# headset-btmodule.net
KiCad netlist of a schematic drawn in EAGLE
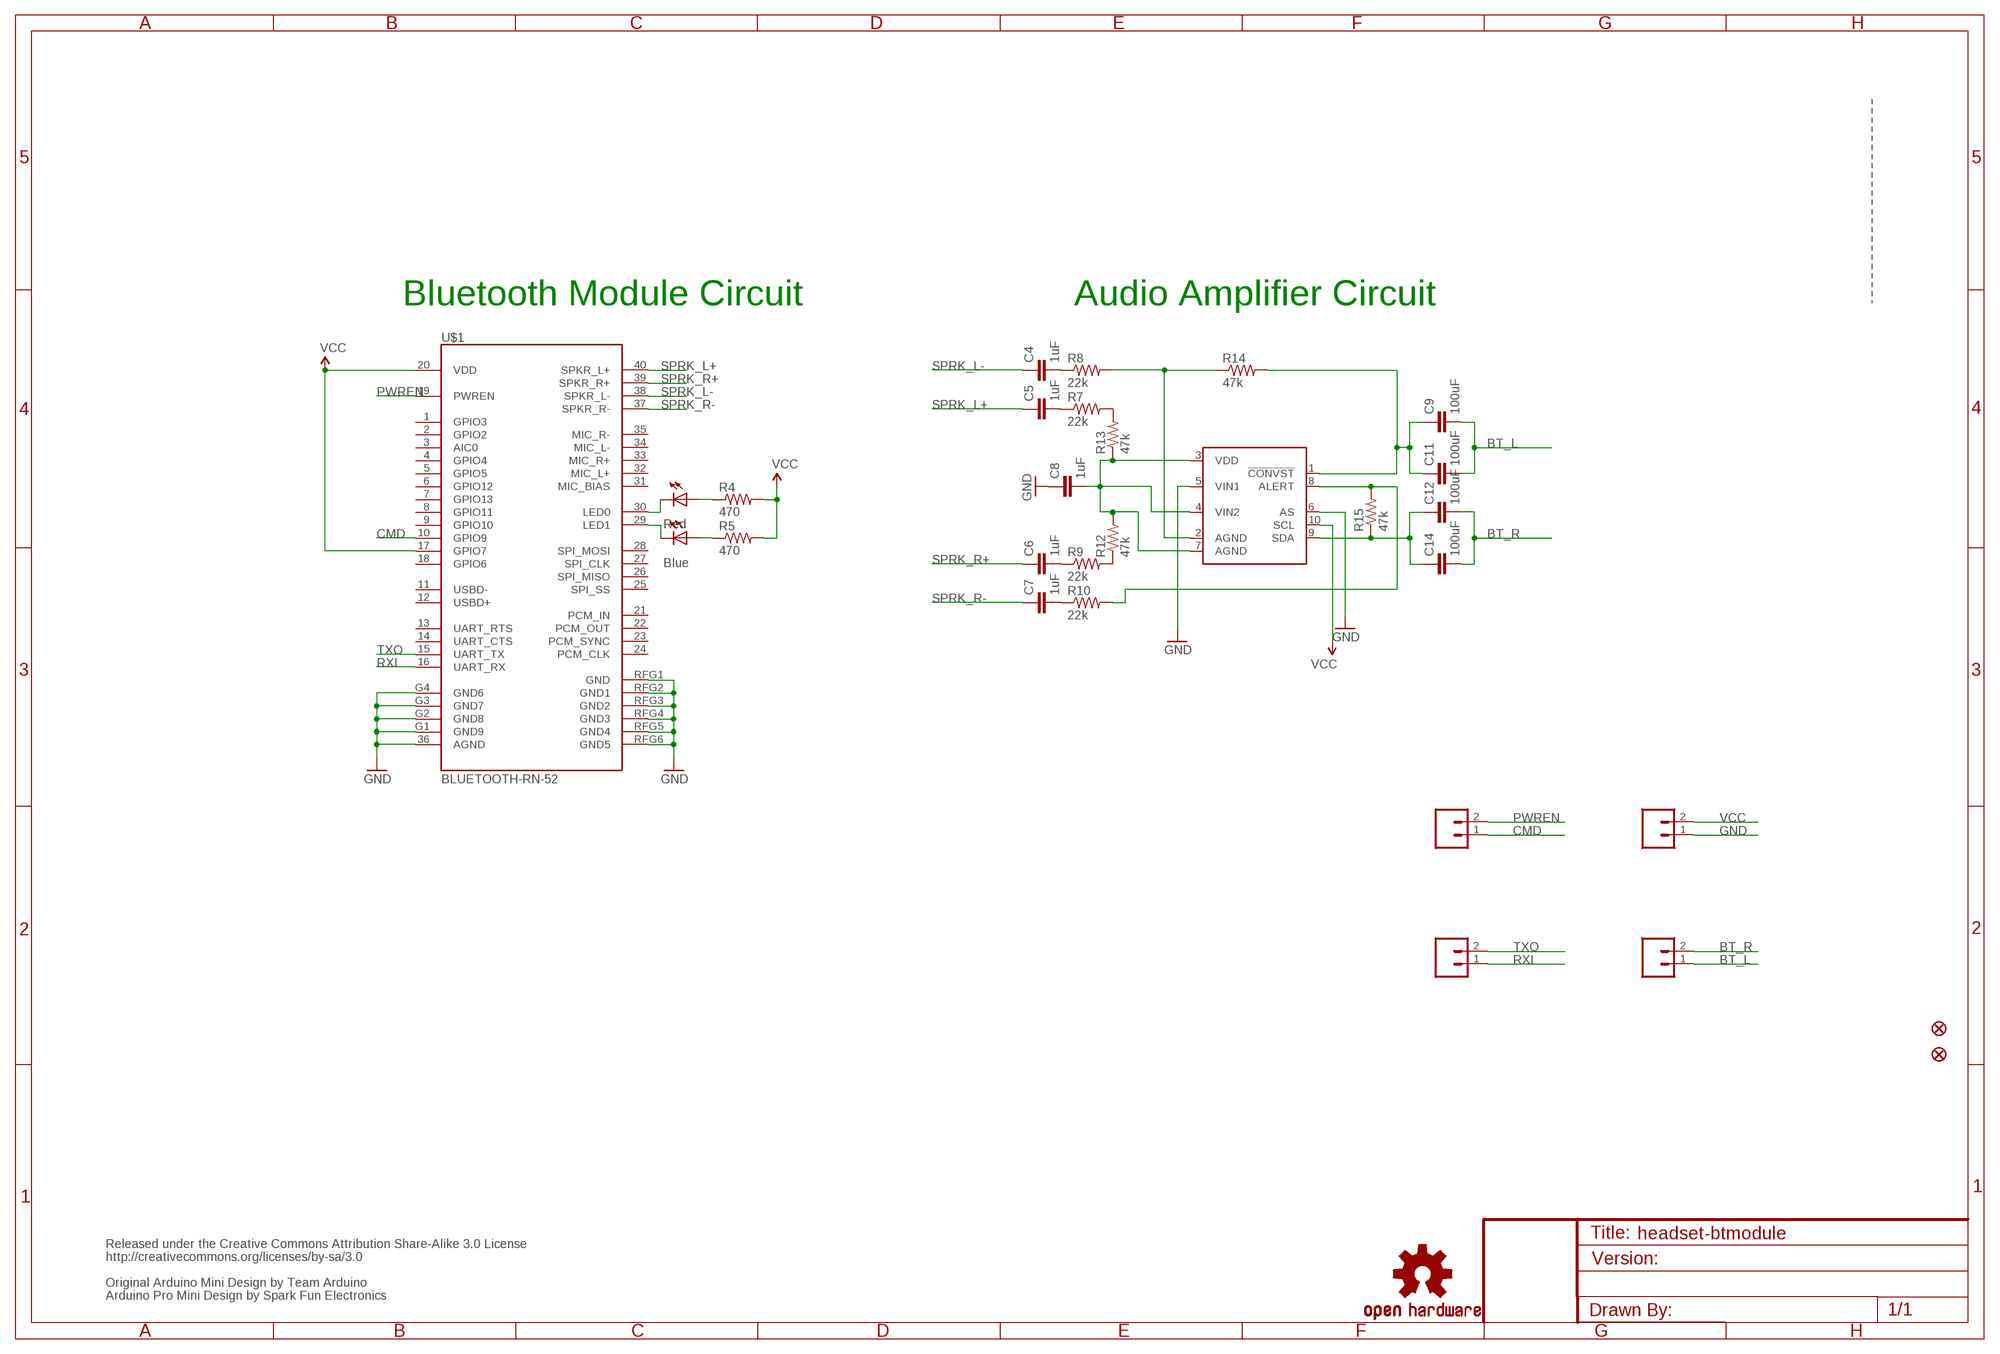
[diagram p0: schematic, sheet 1]

(export (version "E")
  (design (tool "Eeschema 10.0.6"))
  (components
    (comp (ref "AUDIO")
      (value "M02PTH")
      (footprint "eagle-import:1X02")
      (libsource (lib "eagle-import") (part "M02PTH"))
    )
    (comp (ref "C4")
      (value "1uF")
      (footprint "eagle-import:0402-CAP")
      (libsource (lib "eagle-import") (part "CAP0402-CAP"))
    )
    (comp (ref "C5")
      (value "1uF")
      (footprint "eagle-import:0402-CAP")
      (libsource (lib "eagle-import") (part "CAP0402-CAP"))
    )
    (comp (ref "C6")
      (value "1uF")
      (footprint "eagle-import:0402-CAP")
      (libsource (lib "eagle-import") (part "CAP0402-CAP"))
    )
    (comp (ref "C7")
      (value "1uF")
      (footprint "eagle-import:0402-CAP")
      (libsource (lib "eagle-import") (part "CAP0402-CAP"))
    )
    (comp (ref "C8")
      (value "1uF")
      (footprint "eagle-import:0402-CAP")
      (libsource (lib "eagle-import") (part "CAP0402-CAP"))
    )
    (comp (ref "C9")
      (value "100uF")
      (footprint "eagle-import:0805")
      (libsource (lib "eagle-import") (part "CAP0805"))
    )
    (comp (ref "C11")
      (value "100uF")
      (footprint "eagle-import:0805")
      (libsource (lib "eagle-import") (part "CAP0805"))
    )
    (comp (ref "C12")
      (value "100uF")
      (footprint "eagle-import:0805")
      (libsource (lib "eagle-import") (part "CAP0805"))
    )
    (comp (ref "C14")
      (value "100uF")
      (footprint "eagle-import:0805")
      (libsource (lib "eagle-import") (part "CAP0805"))
    )
    (comp (ref "CMD")
      (value "M02PTH")
      (footprint "eagle-import:1X02")
      (libsource (lib "eagle-import") (part "M02PTH"))
    )
    (comp (ref "JP5")
      (value "FIDUCIALUFIDUCIAL")
      (footprint "eagle-import:MICRO-FIDUCIAL")
      (libsource (lib "eagle-import") (part "FIDUCIALUFIDUCIAL"))
    )
    (comp (ref "JP8")
      (value "FIDUCIALUFIDUCIAL")
      (footprint "eagle-import:MICRO-FIDUCIAL")
      (libsource (lib "eagle-import") (part "FIDUCIALUFIDUCIAL"))
    )
    (comp (ref "LED3")
      (value "Red")
      (footprint "eagle-import:LED3MM-NS")
      (libsource (lib "eagle-import") (part "LED-3MM-NO_SILK"))
    )
    (comp (ref "LED4")
      (value "Blue")
      (footprint "eagle-import:LED3MM-NS")
      (libsource (lib "eagle-import") (part "LED-3MM-NO_SILK"))
    )
    (comp (ref "POWER")
      (value "M02PTH")
      (footprint "eagle-import:1X02")
      (libsource (lib "eagle-import") (part "M02PTH"))
    )
    (comp (ref "R4")
      (value "470")
      (footprint "eagle-import:0402-RES")
      (libsource (lib "eagle-import") (part "RESISTOR0402-RES"))
    )
    (comp (ref "R5")
      (value "470")
      (footprint "eagle-import:0402-RES")
      (libsource (lib "eagle-import") (part "RESISTOR0402-RES"))
    )
    (comp (ref "R7")
      (value "22k")
      (footprint "eagle-import:0402-RES")
      (libsource (lib "eagle-import") (part "RESISTOR0402-RES"))
    )
    (comp (ref "R8")
      (value "22k")
      (footprint "eagle-import:0402-RES")
      (libsource (lib "eagle-import") (part "RESISTOR0402-RES"))
    )
    (comp (ref "R9")
      (value "22k")
      (footprint "eagle-import:0402-RES")
      (libsource (lib "eagle-import") (part "RESISTOR0402-RES"))
    )
    (comp (ref "R10")
      (value "22k")
      (footprint "eagle-import:0402-RES")
      (libsource (lib "eagle-import") (part "RESISTOR0402-RES"))
    )
    (comp (ref "R12")
      (value "47k")
      (footprint "eagle-import:0402-RES")
      (libsource (lib "eagle-import") (part "RESISTOR0402-RES"))
    )
    (comp (ref "R13")
      (value "47k")
      (footprint "eagle-import:0402-RES")
      (libsource (lib "eagle-import") (part "RESISTOR0402-RES"))
    )
    (comp (ref "R14")
      (value "47k")
      (footprint "eagle-import:0402-RES")
      (libsource (lib "eagle-import") (part "RESISTOR0402-RES"))
    )
    (comp (ref "R15")
      (value "47k")
      (footprint "eagle-import:0402-RES")
      (libsource (lib "eagle-import") (part "RESISTOR0402-RES"))
    )
    (comp (ref "T")
      (value "AD7992")
      (footprint "eagle-import:MSOP10")
      (fields (field (name "MPN") "AD7992BRMZ-0"))
      (libsource (lib "eagle-import") (part "AD7992"))
    )
    (comp (ref "TX")
      (value "M02PTH")
      (footprint "eagle-import:1X02")
      (libsource (lib "eagle-import") (part "M02PTH"))
    )
    (comp (ref "U$1")
      (value "BLUETOOTH-RN-52")
      (footprint "eagle-import:RN-52")
      (libsource (lib "eagle-import") (part "BLUETOOTH-RN-52"))
    )
    (comp (ref "U$3")
      (value "OSHW-LOGOS")
      (footprint "eagle-import:OSHW-LOGO-S")
      (libsource (lib "eagle-import") (part "OSHW-LOGOS"))
    )
  )
  (nets
    (net (code "1") (name "/BT_L") (class "Default")
      (node (ref "AUDIO") (pin "1") (pinfunction "1_1") (pintype "passive"))
      (node (ref "C11") (pin "2") (pinfunction "2_2") (pintype "passive"))
      (node (ref "C9") (pin "2") (pinfunction "2_2") (pintype "passive"))
    )
    (net (code "2") (name "/BT_R") (class "Default")
      (node (ref "AUDIO") (pin "2") (pinfunction "2_2") (pintype "passive"))
      (node (ref "C12") (pin "2") (pinfunction "2_2") (pintype "passive"))
      (node (ref "C14") (pin "2") (pinfunction "2_2") (pintype "passive"))
    )
    (net (code "3") (name "/CMD") (class "Default")
      (node (ref "CMD") (pin "1") (pinfunction "1_1") (pintype "passive"))
      (node (ref "U$1") (pin "10") (pinfunction "GPIO9_10") (pintype "bidirectional"))
    )
    (net (code "4") (name "/PWREN") (class "Default")
      (node (ref "CMD") (pin "2") (pinfunction "2_2") (pintype "passive"))
      (node (ref "U$1") (pin "19") (pinfunction "PWREN_19") (pintype "bidirectional"))
    )
    (net (code "5") (name "/RXI") (class "Default")
      (node (ref "TX") (pin "1") (pinfunction "1_1") (pintype "passive"))
      (node (ref "U$1") (pin "16") (pinfunction "UART_RX_16") (pintype "bidirectional"))
    )
    (net (code "6") (name "/SPRK_L+") (class "Default")
      (node (ref "C5") (pin "1") (pinfunction "1_1") (pintype "passive"))
      (node (ref "U$1") (pin "40") (pinfunction "SPKR_L+_40") (pintype "bidirectional"))
    )
    (net (code "7") (name "/SPRK_L-") (class "Default")
      (node (ref "C4") (pin "1") (pinfunction "1_1") (pintype "passive"))
      (node (ref "U$1") (pin "38") (pinfunction "SPKR_L-_38") (pintype "bidirectional"))
    )
    (net (code "8") (name "/SPRK_R+") (class "Default")
      (node (ref "C6") (pin "1") (pinfunction "1_1") (pintype "passive"))
      (node (ref "U$1") (pin "39") (pinfunction "SPKR_R+_39") (pintype "bidirectional"))
    )
    (net (code "9") (name "/SPRK_R-") (class "Default")
      (node (ref "C7") (pin "1") (pinfunction "1_1") (pintype "passive"))
      (node (ref "U$1") (pin "37") (pinfunction "SPKR_R-_37") (pintype "bidirectional"))
    )
    (net (code "10") (name "/TXO") (class "Default")
      (node (ref "TX") (pin "2") (pinfunction "2_2") (pintype "passive"))
      (node (ref "U$1") (pin "15") (pinfunction "UART_TX_15") (pintype "bidirectional"))
    )
    (net (code "11") (name "GND") (class "Default")
      (node (ref "C8") (pin "1") (pinfunction "1_1") (pintype "passive"))
      (node (ref "POWER") (pin "1") (pinfunction "1_1") (pintype "passive"))
      (node (ref "T") (pin "5") (pinfunction "VIN1_5") (pintype "input"))
      (node (ref "T") (pin "6") (pinfunction "AS_6") (pintype "input"))
      (node (ref "U$1") (pin "36") (pinfunction "AGND_36") (pintype "bidirectional"))
      (node (ref "U$1") (pin "G1") (pinfunction "GND9_G1") (pintype "bidirectional"))
      (node (ref "U$1") (pin "G2") (pinfunction "GND8_G2") (pintype "bidirectional"))
      (node (ref "U$1") (pin "G3") (pinfunction "GND7_G3") (pintype "bidirectional"))
      (node (ref "U$1") (pin "G4") (pinfunction "GND6_G4") (pintype "bidirectional"))
      (node (ref "U$1") (pin "RFG1") (pinfunction "GND_RFG1") (pintype "bidirectional"))
      (node (ref "U$1") (pin "RFG2") (pinfunction "GND1_RFG2") (pintype "bidirectional"))
      (node (ref "U$1") (pin "RFG3") (pinfunction "GND2_RFG3") (pintype "bidirectional"))
      (node (ref "U$1") (pin "RFG4") (pinfunction "GND3_RFG4") (pintype "bidirectional"))
      (node (ref "U$1") (pin "RFG5") (pinfunction "GND4_RFG5") (pintype "bidirectional"))
      (node (ref "U$1") (pin "RFG6") (pinfunction "GND5_RFG6") (pintype "bidirectional"))
    )
    (net (code "12") (name "Net-(C4-Pad2)") (class "Default")
      (node (ref "C4") (pin "2") (pinfunction "2_2") (pintype "passive"))
      (node (ref "R8") (pin "1") (pinfunction "1_1") (pintype "passive"))
    )
    (net (code "13") (name "Net-(C5-Pad2)") (class "Default")
      (node (ref "C5") (pin "2") (pinfunction "2_2") (pintype "passive"))
      (node (ref "R7") (pin "1") (pinfunction "1_1") (pintype "passive"))
    )
    (net (code "14") (name "Net-(C6-Pad2)") (class "Default")
      (node (ref "C6") (pin "2") (pinfunction "2_2") (pintype "passive"))
      (node (ref "R9") (pin "1") (pinfunction "1_1") (pintype "passive"))
    )
    (net (code "15") (name "Net-(C7-Pad2)") (class "Default")
      (node (ref "C7") (pin "2") (pinfunction "2_2") (pintype "passive"))
      (node (ref "R10") (pin "1") (pinfunction "1_1") (pintype "passive"))
    )
    (net (code "16") (name "Net-(LED3-C)") (class "Default")
      (node (ref "LED3") (pin "K") (pinfunction "C_K") (pintype "passive"))
      (node (ref "U$1") (pin "30") (pinfunction "LED0_30") (pintype "bidirectional"))
    )
    (net (code "17") (name "Net-(LED3-PadA)") (class "Default")
      (node (ref "LED3") (pin "A") (pinfunction "A_A") (pintype "passive"))
      (node (ref "R4") (pin "1") (pinfunction "1_1") (pintype "passive"))
    )
    (net (code "18") (name "Net-(LED4-C)") (class "Default")
      (node (ref "LED4") (pin "K") (pinfunction "C_K") (pintype "passive"))
      (node (ref "U$1") (pin "29") (pinfunction "LED1_29") (pintype "bidirectional"))
    )
    (net (code "19") (name "Net-(LED4-PadA)") (class "Default")
      (node (ref "LED4") (pin "A") (pinfunction "A_A") (pintype "passive"))
      (node (ref "R5") (pin "1") (pinfunction "1_1") (pintype "passive"))
    )
    (net (code "20") (name "Net-(R12-Pad1)") (class "Default")
      (node (ref "R12") (pin "1") (pinfunction "1_1") (pintype "passive"))
      (node (ref "R9") (pin "2") (pinfunction "2_2") (pintype "passive"))
    )
    (net (code "21") (name "Net-(R13-Pad2)") (class "Default")
      (node (ref "R13") (pin "2") (pinfunction "2_2") (pintype "passive"))
      (node (ref "R7") (pin "2") (pinfunction "2_2") (pintype "passive"))
    )
    (net (code "22") (name "Net-(R14-Pad1)") (class "Default")
      (node (ref "R14") (pin "1") (pinfunction "1_1") (pintype "passive"))
      (node (ref "R8") (pin "2") (pinfunction "2_2") (pintype "passive"))
      (node (ref "T") (pin "2") (pinfunction "AGND_2") (pintype "power_in"))
    )
    (net (code "23") (name "Net-(T-ALERT)") (class "Default")
      (node (ref "R10") (pin "2") (pinfunction "2_2") (pintype "passive"))
      (node (ref "R15") (pin "2") (pinfunction "2_2") (pintype "passive"))
      (node (ref "T") (pin "8") (pinfunction "ALERT_8") (pintype "output"))
    )
    (net (code "24") (name "Net-(T-SDA)") (class "Default")
      (node (ref "C12") (pin "1") (pinfunction "1_1") (pintype "passive"))
      (node (ref "C14") (pin "1") (pinfunction "1_1") (pintype "passive"))
      (node (ref "R15") (pin "1") (pinfunction "1_1") (pintype "passive"))
      (node (ref "T") (pin "9") (pinfunction "SDA_9") (pintype "bidirectional"))
    )
    (net (code "25") (name "Net-(T-VDD)") (class "Default")
      (node (ref "C8") (pin "2") (pinfunction "2_2") (pintype "passive"))
      (node (ref "R12") (pin "2") (pinfunction "2_2") (pintype "passive"))
      (node (ref "R13") (pin "1") (pinfunction "1_1") (pintype "passive"))
      (node (ref "T") (pin "3") (pinfunction "VDD_3") (pintype "power_in"))
      (node (ref "T") (pin "4") (pinfunction "VIN2_4") (pintype "input"))
      (node (ref "T") (pin "7") (pinfunction "AGND_7") (pintype "power_in"))
    )
    (net (code "26") (name "Net-(T-~{CONVST})") (class "Default")
      (node (ref "C11") (pin "1") (pinfunction "1_1") (pintype "passive"))
      (node (ref "C9") (pin "1") (pinfunction "1_1") (pintype "passive"))
      (node (ref "R14") (pin "2") (pinfunction "2_2") (pintype "passive"))
      (node (ref "T") (pin "1") (pinfunction "~{CONVST}_1") (pintype "input"))
    )
    (net (code "27") (name "VCC") (class "Default")
      (node (ref "POWER") (pin "2") (pinfunction "2_2") (pintype "passive"))
      (node (ref "R4") (pin "2") (pinfunction "2_2") (pintype "passive"))
      (node (ref "R5") (pin "2") (pinfunction "2_2") (pintype "passive"))
      (node (ref "T") (pin "10") (pinfunction "SCL_10") (pintype "input"))
      (node (ref "U$1") (pin "17") (pinfunction "GPIO7_17") (pintype "bidirectional"))
      (node (ref "U$1") (pin "20") (pinfunction "VDD_20") (pintype "bidirectional"))
    )
    (net (code "28") (name "unconnected-(U$1-AIC0-Pad3)") (class "Default")
      (node (ref "U$1") (pin "3") (pinfunction "AIC0_3") (pintype "bidirectional"))
    )
    (net (code "29") (name "unconnected-(U$1-GPIO2-Pad2)") (class "Default")
      (node (ref "U$1") (pin "2") (pinfunction "GPIO2_2") (pintype "bidirectional"))
    )
    (net (code "30") (name "unconnected-(U$1-GPIO3-Pad1)") (class "Default")
      (node (ref "U$1") (pin "1") (pinfunction "GPIO3_1") (pintype "bidirectional"))
    )
    (net (code "31") (name "unconnected-(U$1-GPIO4-Pad4)") (class "Default")
      (node (ref "U$1") (pin "4") (pinfunction "GPIO4_4") (pintype "bidirectional"))
    )
    (net (code "32") (name "unconnected-(U$1-GPIO5-Pad5)") (class "Default")
      (node (ref "U$1") (pin "5") (pinfunction "GPIO5_5") (pintype "bidirectional"))
    )
    (net (code "33") (name "unconnected-(U$1-GPIO6-Pad18)") (class "Default")
      (node (ref "U$1") (pin "18") (pinfunction "GPIO6_18") (pintype "bidirectional"))
    )
    (net (code "34") (name "unconnected-(U$1-GPIO10-Pad9)") (class "Default")
      (node (ref "U$1") (pin "9") (pinfunction "GPIO10_9") (pintype "bidirectional"))
    )
    (net (code "35") (name "unconnected-(U$1-GPIO11-Pad8)") (class "Default")
      (node (ref "U$1") (pin "8") (pinfunction "GPIO11_8") (pintype "bidirectional"))
    )
    (net (code "36") (name "unconnected-(U$1-GPIO12-Pad6)") (class "Default")
      (node (ref "U$1") (pin "6") (pinfunction "GPIO12_6") (pintype "bidirectional"))
    )
    (net (code "37") (name "unconnected-(U$1-GPIO13-Pad7)") (class "Default")
      (node (ref "U$1") (pin "7") (pinfunction "GPIO13_7") (pintype "bidirectional"))
    )
    (net (code "38") (name "unconnected-(U$1-MIC_BIAS-Pad31)") (class "Default")
      (node (ref "U$1") (pin "31") (pinfunction "MIC_BIAS_31") (pintype "bidirectional"))
    )
    (net (code "39") (name "unconnected-(U$1-MIC_L+-Pad32)") (class "Default")
      (node (ref "U$1") (pin "32") (pinfunction "MIC_L+_32") (pintype "bidirectional"))
    )
    (net (code "40") (name "unconnected-(U$1-MIC_L--Pad34)") (class "Default")
      (node (ref "U$1") (pin "34") (pinfunction "MIC_L-_34") (pintype "bidirectional"))
    )
    (net (code "41") (name "unconnected-(U$1-MIC_R+-Pad33)") (class "Default")
      (node (ref "U$1") (pin "33") (pinfunction "MIC_R+_33") (pintype "bidirectional"))
    )
    (net (code "42") (name "unconnected-(U$1-MIC_R--Pad35)") (class "Default")
      (node (ref "U$1") (pin "35") (pinfunction "MIC_R-_35") (pintype "bidirectional"))
    )
    (net (code "43") (name "unconnected-(U$1-PCM_CLK-Pad24)") (class "Default")
      (node (ref "U$1") (pin "24") (pinfunction "PCM_CLK_24") (pintype "bidirectional"))
    )
    (net (code "44") (name "unconnected-(U$1-PCM_IN-Pad21)") (class "Default")
      (node (ref "U$1") (pin "21") (pinfunction "PCM_IN_21") (pintype "bidirectional"))
    )
    (net (code "45") (name "unconnected-(U$1-PCM_OUT-Pad22)") (class "Default")
      (node (ref "U$1") (pin "22") (pinfunction "PCM_OUT_22") (pintype "bidirectional"))
    )
    (net (code "46") (name "unconnected-(U$1-PCM_SYNC-Pad23)") (class "Default")
      (node (ref "U$1") (pin "23") (pinfunction "PCM_SYNC_23") (pintype "bidirectional"))
    )
    (net (code "47") (name "unconnected-(U$1-SPI_CLK-Pad27)") (class "Default")
      (node (ref "U$1") (pin "27") (pinfunction "SPI_CLK_27") (pintype "bidirectional"))
    )
    (net (code "48") (name "unconnected-(U$1-SPI_MISO-Pad26)") (class "Default")
      (node (ref "U$1") (pin "26") (pinfunction "SPI_MISO_26") (pintype "bidirectional"))
    )
    (net (code "49") (name "unconnected-(U$1-SPI_MOSI-Pad28)") (class "Default")
      (node (ref "U$1") (pin "28") (pinfunction "SPI_MOSI_28") (pintype "bidirectional"))
    )
    (net (code "50") (name "unconnected-(U$1-SPI_SS-Pad25)") (class "Default")
      (node (ref "U$1") (pin "25") (pinfunction "SPI_SS_25") (pintype "bidirectional"))
    )
    (net (code "51") (name "unconnected-(U$1-UART_CTS-Pad14)") (class "Default")
      (node (ref "U$1") (pin "14") (pinfunction "UART_CTS_14") (pintype "bidirectional"))
    )
    (net (code "52") (name "unconnected-(U$1-UART_RTS-Pad13)") (class "Default")
      (node (ref "U$1") (pin "13") (pinfunction "UART_RTS_13") (pintype "bidirectional"))
    )
    (net (code "53") (name "unconnected-(U$1-USBD+-Pad12)") (class "Default")
      (node (ref "U$1") (pin "12") (pinfunction "USBD+_12") (pintype "bidirectional"))
    )
    (net (code "54") (name "unconnected-(U$1-USBD--Pad11)") (class "Default")
      (node (ref "U$1") (pin "11") (pinfunction "USBD-_11") (pintype "bidirectional"))
    )
  )
)
